# 09-STM32-02.net
KiCad netlist of a schematic drawn in Altium Designer
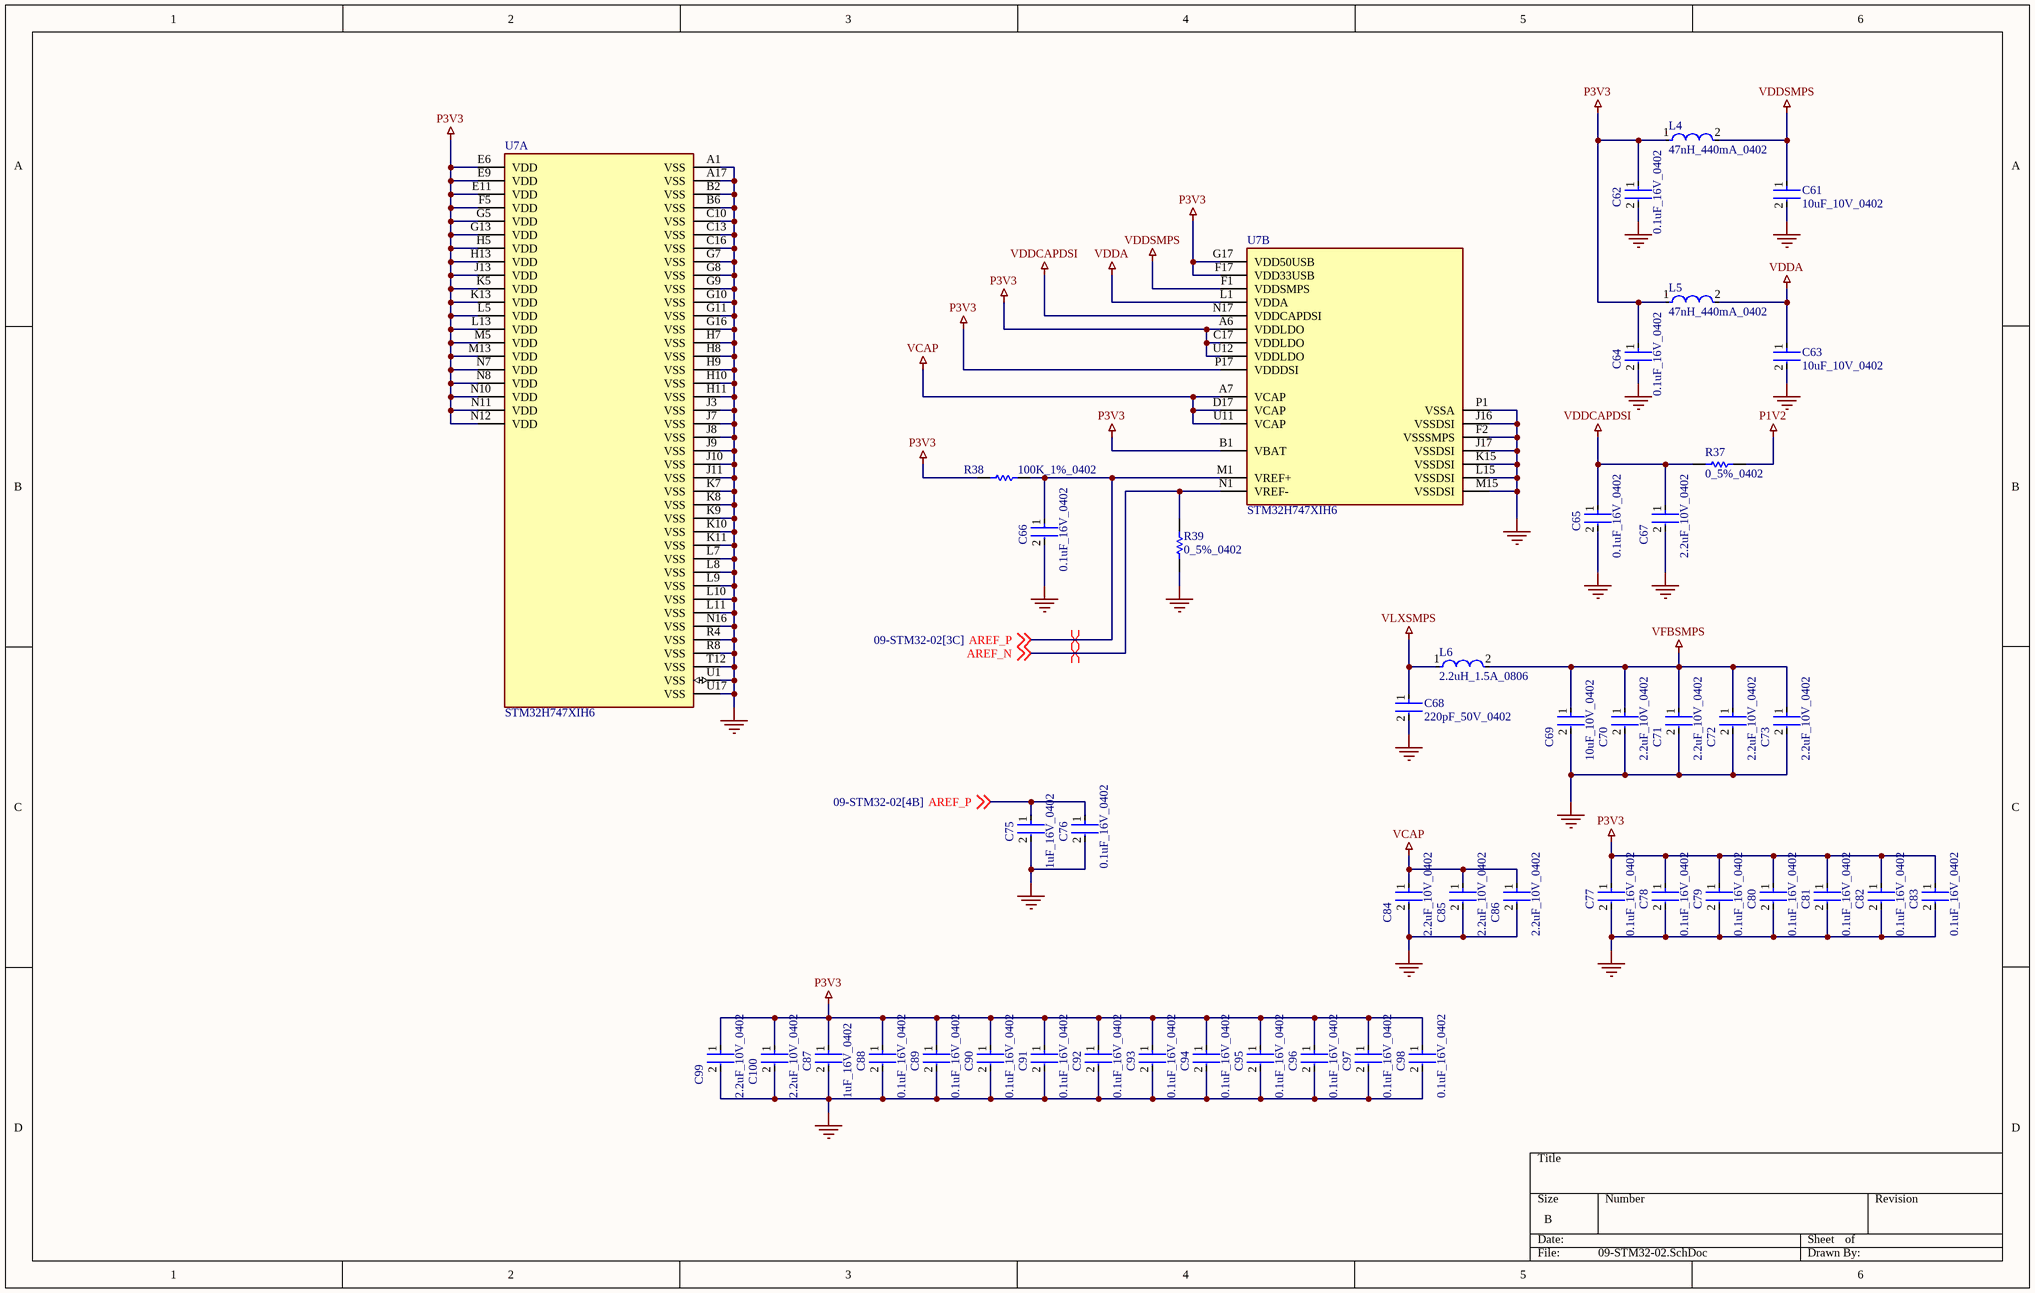
[diagram p0: 09-STM32-02.SchDoc]

(export (version "E")
  (design (tool "Eeschema 10.0.6"))
  (components
    (comp (ref "C61")
      (value "10uF_10V_0402")
      (footprint "FP-CL05A106MP5NUNC-MFG")
      (description "CAP CER 10UF 10V X5R 0402")
      (fields
        (field (name "OCTOPART") "https://octopart.com/cl05a106mp5nunc-samsung-22457395")
        (field (name "TOLERANCE") "20%")
      )
      (libsource (lib "Altium Content Vault") (part "b4654b650e69147ec39a6b967a45e02"))
    )
    (comp (ref "C62")
      (value "0.1uF_16V_0402")
      (footprint "FP-C0402-BB-MFG")
      (description "CAP CER 0.1UF 16V 5% X7R 0402")
      (fields
        (field (name "MANUFACTURER") "Kemet")
        (field (name "MANUFACTURER PART NUMBER") "C0402C104J4RACTU")
      )
      (libsource (lib "Altium Content Vault") (part "b4654b650e69147ec39a6b967a45e02"))
    )
    (comp (ref "C63")
      (value "10uF_10V_0402")
      (footprint "FP-CL05A106MP5NUNC-MFG")
      (description "CAP CER 10UF 10V X5R 0402")
      (fields
        (field (name "OCTOPART") "https://octopart.com/cl05a106mp5nunc-samsung-22457395")
        (field (name "TOLERANCE") "20%")
      )
      (libsource (lib "Altium Content Vault") (part "b4654b650e69147ec39a6b967a45e02"))
    )
    (comp (ref "C64")
      (value "0.1uF_16V_0402")
      (footprint "FP-C0402-BB-MFG")
      (description "CAP CER 0.1UF 16V 5% X7R 0402")
      (fields
        (field (name "MANUFACTURER") "Kemet")
        (field (name "MANUFACTURER PART NUMBER") "C0402C104J4RACTU")
      )
      (libsource (lib "Altium Content Vault") (part "b4654b650e69147ec39a6b967a45e02"))
    )
    (comp (ref "C65")
      (value "0.1uF_16V_0402")
      (footprint "FP-C0402-BB-MFG")
      (description "CAP CER 0.1UF 16V 5% X7R 0402")
      (fields
        (field (name "MANUFACTURER") "Kemet")
        (field (name "MANUFACTURER PART NUMBER") "C0402C104J4RACTU")
      )
      (libsource (lib "Altium Content Vault") (part "b4654b650e69147ec39a6b967a45e02"))
    )
    (comp (ref "C66")
      (value "0.1uF_16V_0402")
      (footprint "FP-C0402-BB-MFG")
      (description "CAP CER 0.1UF 16V 5% X7R 0402")
      (fields
        (field (name "MANUFACTURER") "Kemet")
        (field (name "MANUFACTURER PART NUMBER") "C0402C104J4RACTU")
      )
      (libsource (lib "Altium Content Vault") (part "b4654b650e69147ec39a6b967a45e02"))
    )
    (comp (ref "C67")
      (value "2.2uF_10V_0402")
      (footprint "FP-C1005-050-0_15-0_1-MFG")
      (description "CAP CER 2.2UF 10V X7S 0402")
      (fields (field (name "TOLERANCE") "10%"))
      (libsource (lib "Altium Content Vault") (part "b4654b650e69147ec39a6b967a45e02"))
    )
    (comp (ref "C68")
      (value "220pF_50V_0402")
      (footprint "FP-GCM155-0_05-IPC_C")
      (description "Ceramic Capacitor for Automotive 220pF ±10% 50VDC X7R 0402 Paper T/R")
      (fields (field (name "TOLERANCE") "10%") (field (name "VOLTAGE") "50V"))
      (libsource (lib "Altium Content Vault") (part "02cd4be3c70576c341d710602a673aa"))
    )
    (comp (ref "C69")
      (value "10uF_10V_0402")
      (footprint "FP-CL05A106MP5NUNC-MFG")
      (description "CAP CER 10UF 10V X5R 0402")
      (fields
        (field (name "OCTOPART") "https://octopart.com/cl05a106mp5nunc-samsung-22457395")
        (field (name "TOLERANCE") "20%")
      )
      (libsource (lib "Altium Content Vault") (part "b4654b650e69147ec39a6b967a45e02"))
    )
    (comp (ref "C70")
      (value "2.2uF_10V_0402")
      (footprint "FP-C1005-050-0_15-0_1-MFG")
      (description "CAP CER 2.2UF 10V X7S 0402")
      (fields (field (name "TOLERANCE") "10%"))
      (libsource (lib "Altium Content Vault") (part "b4654b650e69147ec39a6b967a45e02"))
    )
    (comp (ref "C71")
      (value "2.2uF_10V_0402")
      (footprint "FP-C1005-050-0_15-0_1-MFG")
      (description "CAP CER 2.2UF 10V X7S 0402")
      (fields (field (name "TOLERANCE") "10%"))
      (libsource (lib "Altium Content Vault") (part "b4654b650e69147ec39a6b967a45e02"))
    )
    (comp (ref "C72")
      (value "2.2uF_10V_0402")
      (footprint "FP-C1005-050-0_15-0_1-MFG")
      (description "CAP CER 2.2UF 10V X7S 0402")
      (fields (field (name "TOLERANCE") "10%"))
      (libsource (lib "Altium Content Vault") (part "b4654b650e69147ec39a6b967a45e02"))
    )
    (comp (ref "C73")
      (value "2.2uF_10V_0402")
      (footprint "FP-C1005-050-0_15-0_1-MFG")
      (description "CAP CER 2.2UF 10V X7S 0402")
      (fields (field (name "TOLERANCE") "10%"))
      (libsource (lib "Altium Content Vault") (part "b4654b650e69147ec39a6b967a45e02"))
    )
    (comp (ref "C75")
      (value "1uF_16V_0402")
      (footprint "FP-0402-L_1_0_0_05-W_0_5-IPC_A")
      (description "None")
      (fields (field (name "TOLERANCE") "10%"))
      (libsource (lib "Altium Content Vault") (part "b4654b650e69147ec39a6b967a45e02"))
    )
    (comp (ref "C76")
      (value "0.1uF_16V_0402")
      (footprint "FP-C0402-BB-MFG")
      (description "CAP CER 0.1UF 16V 5% X7R 0402")
      (fields
        (field (name "MANUFACTURER") "Kemet")
        (field (name "MANUFACTURER PART NUMBER") "C0402C104J4RACTU")
      )
      (libsource (lib "Altium Content Vault") (part "b4654b650e69147ec39a6b967a45e02"))
    )
    (comp (ref "C77")
      (value "0.1uF_16V_0402")
      (footprint "FP-C0402-BB-MFG")
      (description "CAP CER 0.1UF 16V 5% X7R 0402")
      (fields
        (field (name "MANUFACTURER") "Kemet")
        (field (name "MANUFACTURER PART NUMBER") "C0402C104J4RACTU")
      )
      (libsource (lib "Altium Content Vault") (part "b4654b650e69147ec39a6b967a45e02"))
    )
    (comp (ref "C78")
      (value "0.1uF_16V_0402")
      (footprint "FP-C0402-BB-MFG")
      (description "CAP CER 0.1UF 16V 5% X7R 0402")
      (fields
        (field (name "MANUFACTURER") "Kemet")
        (field (name "MANUFACTURER PART NUMBER") "C0402C104J4RACTU")
      )
      (libsource (lib "Altium Content Vault") (part "b4654b650e69147ec39a6b967a45e02"))
    )
    (comp (ref "C79")
      (value "0.1uF_16V_0402")
      (footprint "FP-C0402-BB-MFG")
      (description "CAP CER 0.1UF 16V 5% X7R 0402")
      (fields
        (field (name "MANUFACTURER") "Kemet")
        (field (name "MANUFACTURER PART NUMBER") "C0402C104J4RACTU")
      )
      (libsource (lib "Altium Content Vault") (part "b4654b650e69147ec39a6b967a45e02"))
    )
    (comp (ref "C80")
      (value "0.1uF_16V_0402")
      (footprint "FP-C0402-BB-MFG")
      (description "CAP CER 0.1UF 16V 5% X7R 0402")
      (fields
        (field (name "MANUFACTURER") "Kemet")
        (field (name "MANUFACTURER PART NUMBER") "C0402C104J4RACTU")
      )
      (libsource (lib "Altium Content Vault") (part "b4654b650e69147ec39a6b967a45e02"))
    )
    (comp (ref "C81")
      (value "0.1uF_16V_0402")
      (footprint "FP-C0402-BB-MFG")
      (description "CAP CER 0.1UF 16V 5% X7R 0402")
      (fields
        (field (name "MANUFACTURER") "Kemet")
        (field (name "MANUFACTURER PART NUMBER") "C0402C104J4RACTU")
      )
      (libsource (lib "Altium Content Vault") (part "b4654b650e69147ec39a6b967a45e02"))
    )
    (comp (ref "C82")
      (value "0.1uF_16V_0402")
      (footprint "FP-C0402-BB-MFG")
      (description "CAP CER 0.1UF 16V 5% X7R 0402")
      (fields
        (field (name "MANUFACTURER") "Kemet")
        (field (name "MANUFACTURER PART NUMBER") "C0402C104J4RACTU")
      )
      (libsource (lib "Altium Content Vault") (part "b4654b650e69147ec39a6b967a45e02"))
    )
    (comp (ref "C83")
      (value "0.1uF_16V_0402")
      (footprint "FP-C0402-BB-MFG")
      (description "CAP CER 0.1UF 16V 5% X7R 0402")
      (fields
        (field (name "MANUFACTURER") "Kemet")
        (field (name "MANUFACTURER PART NUMBER") "C0402C104J4RACTU")
      )
      (libsource (lib "Altium Content Vault") (part "b4654b650e69147ec39a6b967a45e02"))
    )
    (comp (ref "C84")
      (value "2.2uF_10V_0402")
      (footprint "FP-C1005-050-0_15-0_1-MFG")
      (description "CAP CER 2.2UF 10V X7S 0402")
      (fields (field (name "TOLERANCE") "10%"))
      (libsource (lib "Altium Content Vault") (part "b4654b650e69147ec39a6b967a45e02"))
    )
    (comp (ref "C85")
      (value "2.2uF_10V_0402")
      (footprint "FP-C1005-050-0_15-0_1-MFG")
      (description "CAP CER 2.2UF 10V X7S 0402")
      (fields (field (name "TOLERANCE") "10%"))
      (libsource (lib "Altium Content Vault") (part "b4654b650e69147ec39a6b967a45e02"))
    )
    (comp (ref "C86")
      (value "2.2uF_10V_0402")
      (footprint "FP-C1005-050-0_15-0_1-MFG")
      (description "CAP CER 2.2UF 10V X7S 0402")
      (fields (field (name "TOLERANCE") "10%"))
      (libsource (lib "Altium Content Vault") (part "b4654b650e69147ec39a6b967a45e02"))
    )
    (comp (ref "C87")
      (value "1uF_16V_0402")
      (footprint "FP-0402-L_1_0_0_05-W_0_5-IPC_A")
      (description "None")
      (fields (field (name "TOLERANCE") "10%"))
      (libsource (lib "Altium Content Vault") (part "b4654b650e69147ec39a6b967a45e02"))
    )
    (comp (ref "C88")
      (value "0.1uF_16V_0402")
      (footprint "FP-C0402-BB-MFG")
      (description "CAP CER 0.1UF 16V 5% X7R 0402")
      (fields
        (field (name "MANUFACTURER") "Kemet")
        (field (name "MANUFACTURER PART NUMBER") "C0402C104J4RACTU")
      )
      (libsource (lib "Altium Content Vault") (part "b4654b650e69147ec39a6b967a45e02"))
    )
    (comp (ref "C89")
      (value "0.1uF_16V_0402")
      (footprint "FP-C0402-BB-MFG")
      (description "CAP CER 0.1UF 16V 5% X7R 0402")
      (fields
        (field (name "MANUFACTURER") "Kemet")
        (field (name "MANUFACTURER PART NUMBER") "C0402C104J4RACTU")
      )
      (libsource (lib "Altium Content Vault") (part "b4654b650e69147ec39a6b967a45e02"))
    )
    (comp (ref "C90")
      (value "0.1uF_16V_0402")
      (footprint "FP-C0402-BB-MFG")
      (description "CAP CER 0.1UF 16V 5% X7R 0402")
      (fields
        (field (name "MANUFACTURER") "Kemet")
        (field (name "MANUFACTURER PART NUMBER") "C0402C104J4RACTU")
      )
      (libsource (lib "Altium Content Vault") (part "b4654b650e69147ec39a6b967a45e02"))
    )
    (comp (ref "C91")
      (value "0.1uF_16V_0402")
      (footprint "FP-C0402-BB-MFG")
      (description "CAP CER 0.1UF 16V 5% X7R 0402")
      (fields
        (field (name "MANUFACTURER") "Kemet")
        (field (name "MANUFACTURER PART NUMBER") "C0402C104J4RACTU")
      )
      (libsource (lib "Altium Content Vault") (part "b4654b650e69147ec39a6b967a45e02"))
    )
    (comp (ref "C92")
      (value "0.1uF_16V_0402")
      (footprint "FP-C0402-BB-MFG")
      (description "CAP CER 0.1UF 16V 5% X7R 0402")
      (fields
        (field (name "MANUFACTURER") "Kemet")
        (field (name "MANUFACTURER PART NUMBER") "C0402C104J4RACTU")
      )
      (libsource (lib "Altium Content Vault") (part "b4654b650e69147ec39a6b967a45e02"))
    )
    (comp (ref "C93")
      (value "0.1uF_16V_0402")
      (footprint "FP-C0402-BB-MFG")
      (description "CAP CER 0.1UF 16V 5% X7R 0402")
      (fields
        (field (name "MANUFACTURER") "Kemet")
        (field (name "MANUFACTURER PART NUMBER") "C0402C104J4RACTU")
      )
      (libsource (lib "Altium Content Vault") (part "b4654b650e69147ec39a6b967a45e02"))
    )
    (comp (ref "C94")
      (value "0.1uF_16V_0402")
      (footprint "FP-C0402-BB-MFG")
      (description "CAP CER 0.1UF 16V 5% X7R 0402")
      (fields
        (field (name "MANUFACTURER") "Kemet")
        (field (name "MANUFACTURER PART NUMBER") "C0402C104J4RACTU")
      )
      (libsource (lib "Altium Content Vault") (part "b4654b650e69147ec39a6b967a45e02"))
    )
    (comp (ref "C95")
      (value "0.1uF_16V_0402")
      (footprint "FP-C0402-BB-MFG")
      (description "CAP CER 0.1UF 16V 5% X7R 0402")
      (fields
        (field (name "MANUFACTURER") "Kemet")
        (field (name "MANUFACTURER PART NUMBER") "C0402C104J4RACTU")
      )
      (libsource (lib "Altium Content Vault") (part "b4654b650e69147ec39a6b967a45e02"))
    )
    (comp (ref "C96")
      (value "0.1uF_16V_0402")
      (footprint "FP-C0402-BB-MFG")
      (description "CAP CER 0.1UF 16V 5% X7R 0402")
      (fields
        (field (name "MANUFACTURER") "Kemet")
        (field (name "MANUFACTURER PART NUMBER") "C0402C104J4RACTU")
      )
      (libsource (lib "Altium Content Vault") (part "b4654b650e69147ec39a6b967a45e02"))
    )
    (comp (ref "C97")
      (value "0.1uF_16V_0402")
      (footprint "FP-C0402-BB-MFG")
      (description "CAP CER 0.1UF 16V 5% X7R 0402")
      (fields
        (field (name "MANUFACTURER") "Kemet")
        (field (name "MANUFACTURER PART NUMBER") "C0402C104J4RACTU")
      )
      (libsource (lib "Altium Content Vault") (part "b4654b650e69147ec39a6b967a45e02"))
    )
    (comp (ref "C98")
      (value "0.1uF_16V_0402")
      (footprint "FP-C0402-BB-MFG")
      (description "CAP CER 0.1UF 16V 5% X7R 0402")
      (fields
        (field (name "MANUFACTURER") "Kemet")
        (field (name "MANUFACTURER PART NUMBER") "C0402C104J4RACTU")
      )
      (libsource (lib "Altium Content Vault") (part "b4654b650e69147ec39a6b967a45e02"))
    )
    (comp (ref "C99")
      (value "2.2uF_10V_0402")
      (footprint "FP-C1005-050-0_15-0_1-MFG")
      (description "CAP CER 2.2UF 10V X7S 0402")
      (fields (field (name "TOLERANCE") "10%"))
      (libsource (lib "Altium Content Vault") (part "b4654b650e69147ec39a6b967a45e02"))
    )
    (comp (ref "C100")
      (value "2.2uF_10V_0402")
      (footprint "FP-C1005-050-0_15-0_1-MFG")
      (description "CAP CER 2.2UF 10V X7S 0402")
      (fields (field (name "TOLERANCE") "10%"))
      (libsource (lib "Altium Content Vault") (part "b4654b650e69147ec39a6b967a45e02"))
    )
    (comp (ref "L4")
      (value "47nH_440mA_0402")
      (footprint "FP-LQW15AN_80-MFG")
      (description "Wire Wound RF Inductor 47nH ±5% 440mA 0.648Ω 0402 (1005)")
      (fields (field (name "TOLERANCE") "5%"))
      (libsource (lib "Altium Content Vault") (part "725321dda6339637d4d059423bc1c3c"))
    )
    (comp (ref "L5")
      (value "47nH_440mA_0402")
      (footprint "FP-LQW15AN_80-MFG")
      (description "Wire Wound RF Inductor 47nH ±5% 440mA 0.648Ω 0402 (1005)")
      (fields (field (name "TOLERANCE") "5%"))
      (libsource (lib "Altium Content Vault") (part "725321dda6339637d4d059423bc1c3c"))
    )
    (comp (ref "L6")
      (value "2.2uH_1.5A_0806")
      (footprint "FP-DFE201612C-MFG")
      (description "Shielded Wirewound Inductor 2.2uH 20% 1500mA 0.144Ω 0806 (2016)")
      (fields (field (name "TOLERANCE") "20%"))
      (libsource (lib "Altium Content Vault") (part "725321dda6339637d4d059423bc1c3c"))
    )
    (comp (ref "R37")
      (value "0_5%_0402")
      (footprint "RESC1005X40X25NL05T10")
      (fields (field (name "MANUFACTURER") "Panasonic") (field (name "PART NUMBER") "ERJ-U020R00X"))
      (libsource (lib "Altium Content Vault") (part "RES"))
    )
    (comp (ref "R38")
      (value "100K_1%_0402")
      (footprint "RESC1005X40X25ML05T10")
      (fields (field (name "MANUFACTURER") "Yageo") (field (name "PART NUMBER") "RC0402FR-13100KL"))
      (libsource (lib "Altium Content Vault") (part "RES"))
    )
    (comp (ref "R39")
      (value "0_5%_0402")
      (footprint "RESC1005X40X25NL05T10")
      (fields (field (name "MANUFACTURER") "Panasonic") (field (name "PART NUMBER") "ERJ-U020R00X"))
      (libsource (lib "Altium Content Vault") (part "RES"))
    )
    (comp (ref "U7")
      (value "STM32H747XIH6")
      (footprint "FP-TFBGA240+25-A07U-MFG")
      (description "HIGH-PERFORMANCE AND DSP WITH DP")
      (fields
        (field (name "MANUFACTURER") "STMicroelectronics")
        (field (name "OCTOPART") "https://octopart.com/stm32h747xih6-stmicroelectronics-100293943")
      )
      (libsource (lib "Altium Content Vault") (part "41f839bdfd00d9510c8672f0f410bfb"))
    )
  )
  (nets
    (net (code "1") (name "AREF_N") (class "Default")
      (node (ref "R39") (pin "2") (pinfunction "2_2") (pintype "passive"))
      (node (ref "U7") (pin "N1") (pinfunction "VREF-_N1") (pintype "power_in"))
    )
    (net (code "2") (name "AREF_P") (class "Default")
      (node (ref "C66") (pin "1") (pinfunction "1_1") (pintype "passive"))
      (node (ref "C75") (pin "1") (pinfunction "1_1") (pintype "passive"))
      (node (ref "C76") (pin "1") (pinfunction "1_1") (pintype "passive"))
      (node (ref "R38") (pin "2") (pinfunction "2_2") (pintype "passive"))
      (node (ref "U7") (pin "M1") (pinfunction "VREF+_M1") (pintype "power_in"))
    )
    (net (code "3") (name "GND") (class "Default")
      (node (ref "C100") (pin "2") (pinfunction "2_2") (pintype "passive"))
      (node (ref "C61") (pin "2") (pinfunction "2_2") (pintype "passive"))
      (node (ref "C62") (pin "2") (pinfunction "2_2") (pintype "passive"))
      (node (ref "C63") (pin "2") (pinfunction "2_2") (pintype "passive"))
      (node (ref "C64") (pin "2") (pinfunction "2_2") (pintype "passive"))
      (node (ref "C65") (pin "2") (pinfunction "2_2") (pintype "passive"))
      (node (ref "C66") (pin "2") (pinfunction "2_2") (pintype "passive"))
      (node (ref "C67") (pin "2") (pinfunction "2_2") (pintype "passive"))
      (node (ref "C68") (pin "2") (pinfunction "2_2") (pintype "passive"))
      (node (ref "C69") (pin "2") (pinfunction "2_2") (pintype "passive"))
      (node (ref "C70") (pin "2") (pinfunction "2_2") (pintype "passive"))
      (node (ref "C71") (pin "2") (pinfunction "2_2") (pintype "passive"))
      (node (ref "C72") (pin "2") (pinfunction "2_2") (pintype "passive"))
      (node (ref "C73") (pin "2") (pinfunction "2_2") (pintype "passive"))
      (node (ref "C75") (pin "2") (pinfunction "2_2") (pintype "passive"))
      (node (ref "C76") (pin "2") (pinfunction "2_2") (pintype "passive"))
      (node (ref "C77") (pin "2") (pinfunction "2_2") (pintype "passive"))
      (node (ref "C78") (pin "2") (pinfunction "2_2") (pintype "passive"))
      (node (ref "C79") (pin "2") (pinfunction "2_2") (pintype "passive"))
      (node (ref "C80") (pin "2") (pinfunction "2_2") (pintype "passive"))
      (node (ref "C81") (pin "2") (pinfunction "2_2") (pintype "passive"))
      (node (ref "C82") (pin "2") (pinfunction "2_2") (pintype "passive"))
      (node (ref "C83") (pin "2") (pinfunction "2_2") (pintype "passive"))
      (node (ref "C84") (pin "2") (pinfunction "2_2") (pintype "passive"))
      (node (ref "C85") (pin "2") (pinfunction "2_2") (pintype "passive"))
      (node (ref "C86") (pin "2") (pinfunction "2_2") (pintype "passive"))
      (node (ref "C87") (pin "2") (pinfunction "2_2") (pintype "passive"))
      (node (ref "C88") (pin "2") (pinfunction "2_2") (pintype "passive"))
      (node (ref "C89") (pin "2") (pinfunction "2_2") (pintype "passive"))
      (node (ref "C90") (pin "2") (pinfunction "2_2") (pintype "passive"))
      (node (ref "C91") (pin "2") (pinfunction "2_2") (pintype "passive"))
      (node (ref "C92") (pin "2") (pinfunction "2_2") (pintype "passive"))
      (node (ref "C93") (pin "2") (pinfunction "2_2") (pintype "passive"))
      (node (ref "C94") (pin "2") (pinfunction "2_2") (pintype "passive"))
      (node (ref "C95") (pin "2") (pinfunction "2_2") (pintype "passive"))
      (node (ref "C96") (pin "2") (pinfunction "2_2") (pintype "passive"))
      (node (ref "C97") (pin "2") (pinfunction "2_2") (pintype "passive"))
      (node (ref "C98") (pin "2") (pinfunction "2_2") (pintype "passive"))
      (node (ref "C99") (pin "2") (pinfunction "2_2") (pintype "passive"))
      (node (ref "R39") (pin "1") (pinfunction "1_1") (pintype "passive"))
      (node (ref "U7") (pin "A1") (pinfunction "VSS_A1") (pintype "power_in"))
      (node (ref "U7") (pin "A17") (pinfunction "VSS_A17") (pintype "power_in"))
      (node (ref "U7") (pin "B2") (pinfunction "VSS_B2") (pintype "power_in"))
      (node (ref "U7") (pin "B6") (pinfunction "VSS_B6") (pintype "power_in"))
      (node (ref "U7") (pin "C10") (pinfunction "VSS_C10") (pintype "power_in"))
      (node (ref "U7") (pin "C13") (pinfunction "VSS_C13") (pintype "power_in"))
      (node (ref "U7") (pin "C16") (pinfunction "VSS_C16") (pintype "power_in"))
      (node (ref "U7") (pin "F2") (pinfunction "VSSSMPS_F2") (pintype "power_in"))
      (node (ref "U7") (pin "G10") (pinfunction "VSS_G10") (pintype "power_in"))
      (node (ref "U7") (pin "G11") (pinfunction "VSS_G11") (pintype "power_in"))
      (node (ref "U7") (pin "G16") (pinfunction "VSS_G16") (pintype "power_in"))
      (node (ref "U7") (pin "G7") (pinfunction "VSS_G7") (pintype "power_in"))
      (node (ref "U7") (pin "G8") (pinfunction "VSS_G8") (pintype "power_in"))
      (node (ref "U7") (pin "G9") (pinfunction "VSS_G9") (pintype "power_in"))
      (node (ref "U7") (pin "H10") (pinfunction "VSS_H10") (pintype "power_in"))
      (node (ref "U7") (pin "H11") (pinfunction "VSS_H11") (pintype "power_in"))
      (node (ref "U7") (pin "H7") (pinfunction "VSS_H7") (pintype "power_in"))
      (node (ref "U7") (pin "H8") (pinfunction "VSS_H8") (pintype "power_in"))
      (node (ref "U7") (pin "H9") (pinfunction "VSS_H9") (pintype "power_in"))
      (node (ref "U7") (pin "J10") (pinfunction "VSS_J10") (pintype "power_in"))
      (node (ref "U7") (pin "J11") (pinfunction "VSS_J11") (pintype "power_in"))
      (node (ref "U7") (pin "J16") (pinfunction "VSSDSI_J16") (pintype "power_in"))
      (node (ref "U7") (pin "J17") (pinfunction "VSSDSI_J17") (pintype "power_in"))
      (node (ref "U7") (pin "J3") (pinfunction "VSS_J3") (pintype "power_in"))
      (node (ref "U7") (pin "J7") (pinfunction "VSS_J7") (pintype "power_in"))
      (node (ref "U7") (pin "J8") (pinfunction "VSS_J8") (pintype "power_in"))
      (node (ref "U7") (pin "J9") (pinfunction "VSS_J9") (pintype "power_in"))
      (node (ref "U7") (pin "K10") (pinfunction "VSS_K10") (pintype "power_in"))
      (node (ref "U7") (pin "K11") (pinfunction "VSS_K11") (pintype "power_in"))
      (node (ref "U7") (pin "K15") (pinfunction "VSSDSI_K15") (pintype "power_in"))
      (node (ref "U7") (pin "K7") (pinfunction "VSS_K7") (pintype "power_in"))
      (node (ref "U7") (pin "K8") (pinfunction "VSS_K8") (pintype "power_in"))
      (node (ref "U7") (pin "K9") (pinfunction "VSS_K9") (pintype "power_in"))
      (node (ref "U7") (pin "L10") (pinfunction "VSS_L10") (pintype "power_in"))
      (node (ref "U7") (pin "L11") (pinfunction "VSS_L11") (pintype "power_in"))
      (node (ref "U7") (pin "L15") (pinfunction "VSSDSI_L15") (pintype "power_in"))
      (node (ref "U7") (pin "L7") (pinfunction "VSS_L7") (pintype "power_in"))
      (node (ref "U7") (pin "L8") (pinfunction "VSS_L8") (pintype "power_in"))
      (node (ref "U7") (pin "L9") (pinfunction "VSS_L9") (pintype "power_in"))
      (node (ref "U7") (pin "M15") (pinfunction "VSSDSI_M15") (pintype "power_in"))
      (node (ref "U7") (pin "N16") (pinfunction "VSS_N16") (pintype "power_in"))
      (node (ref "U7") (pin "P1") (pinfunction "VSSA_P1") (pintype "power_in"))
      (node (ref "U7") (pin "R4") (pinfunction "VSS_R4") (pintype "power_in"))
      (node (ref "U7") (pin "R8") (pinfunction "VSS_R8") (pintype "power_in"))
      (node (ref "U7") (pin "T12") (pinfunction "VSS_T12") (pintype "power_in"))
      (node (ref "U7") (pin "U1") (pinfunction "VSS_U1") (pintype "bidirectional"))
      (node (ref "U7") (pin "U17") (pinfunction "VSS_U17") (pintype "power_in"))
    )
    (net (code "4") (name "P1V2") (class "Default")
      (node (ref "R37") (pin "1") (pinfunction "1_1") (pintype "passive"))
    )
    (net (code "5") (name "P3V3") (class "Default")
      (node (ref "C100") (pin "1") (pinfunction "1_1") (pintype "passive"))
      (node (ref "C62") (pin "1") (pinfunction "1_1") (pintype "passive"))
      (node (ref "C64") (pin "1") (pinfunction "1_1") (pintype "passive"))
      (node (ref "C77") (pin "1") (pinfunction "1_1") (pintype "passive"))
      (node (ref "C78") (pin "1") (pinfunction "1_1") (pintype "passive"))
      (node (ref "C79") (pin "1") (pinfunction "1_1") (pintype "passive"))
      (node (ref "C80") (pin "1") (pinfunction "1_1") (pintype "passive"))
      (node (ref "C81") (pin "1") (pinfunction "1_1") (pintype "passive"))
      (node (ref "C82") (pin "1") (pinfunction "1_1") (pintype "passive"))
      (node (ref "C83") (pin "1") (pinfunction "1_1") (pintype "passive"))
      (node (ref "C87") (pin "1") (pinfunction "1_1") (pintype "passive"))
      (node (ref "C88") (pin "1") (pinfunction "1_1") (pintype "passive"))
      (node (ref "C89") (pin "1") (pinfunction "1_1") (pintype "passive"))
      (node (ref "C90") (pin "1") (pinfunction "1_1") (pintype "passive"))
      (node (ref "C91") (pin "1") (pinfunction "1_1") (pintype "passive"))
      (node (ref "C92") (pin "1") (pinfunction "1_1") (pintype "passive"))
      (node (ref "C93") (pin "1") (pinfunction "1_1") (pintype "passive"))
      (node (ref "C94") (pin "1") (pinfunction "1_1") (pintype "passive"))
      (node (ref "C95") (pin "1") (pinfunction "1_1") (pintype "passive"))
      (node (ref "C96") (pin "1") (pinfunction "1_1") (pintype "passive"))
      (node (ref "C97") (pin "1") (pinfunction "1_1") (pintype "passive"))
      (node (ref "C98") (pin "1") (pinfunction "1_1") (pintype "passive"))
      (node (ref "C99") (pin "1") (pinfunction "1_1") (pintype "passive"))
      (node (ref "L4") (pin "1") (pinfunction "1_1") (pintype "passive"))
      (node (ref "L5") (pin "1") (pinfunction "1_1") (pintype "passive"))
      (node (ref "R38") (pin "1") (pinfunction "1_1") (pintype "passive"))
      (node (ref "U7") (pin "A6") (pinfunction "VDDLDO_A6") (pintype "power_in"))
      (node (ref "U7") (pin "B1") (pinfunction "VBAT_B1") (pintype "power_in"))
      (node (ref "U7") (pin "C17") (pinfunction "VDDLDO_C17") (pintype "power_in"))
      (node (ref "U7") (pin "E11") (pinfunction "VDD_E11") (pintype "power_in"))
      (node (ref "U7") (pin "E6") (pinfunction "VDD_E6") (pintype "power_in"))
      (node (ref "U7") (pin "E9") (pinfunction "VDD_E9") (pintype "power_in"))
      (node (ref "U7") (pin "F17") (pinfunction "VDD33USB_F17") (pintype "power_in"))
      (node (ref "U7") (pin "F5") (pinfunction "VDD_F5") (pintype "power_in"))
      (node (ref "U7") (pin "G13") (pinfunction "VDD_G13") (pintype "power_in"))
      (node (ref "U7") (pin "G17") (pinfunction "VDD50USB_G17") (pintype "power_in"))
      (node (ref "U7") (pin "G5") (pinfunction "VDD_G5") (pintype "power_in"))
      (node (ref "U7") (pin "H13") (pinfunction "VDD_H13") (pintype "power_in"))
      (node (ref "U7") (pin "H5") (pinfunction "VDD_H5") (pintype "power_in"))
      (node (ref "U7") (pin "J13") (pinfunction "VDD_J13") (pintype "power_in"))
      (node (ref "U7") (pin "K13") (pinfunction "VDD_K13") (pintype "power_in"))
      (node (ref "U7") (pin "K5") (pinfunction "VDD_K5") (pintype "power_in"))
      (node (ref "U7") (pin "L13") (pinfunction "VDD_L13") (pintype "power_in"))
      (node (ref "U7") (pin "L5") (pinfunction "VDD_L5") (pintype "power_in"))
      (node (ref "U7") (pin "M13") (pinfunction "VDD_M13") (pintype "power_in"))
      (node (ref "U7") (pin "M5") (pinfunction "VDD_M5") (pintype "power_in"))
      (node (ref "U7") (pin "N10") (pinfunction "VDD_N10") (pintype "power_in"))
      (node (ref "U7") (pin "N11") (pinfunction "VDD_N11") (pintype "power_in"))
      (node (ref "U7") (pin "N12") (pinfunction "VDD_N12") (pintype "power_in"))
      (node (ref "U7") (pin "N7") (pinfunction "VDD_N7") (pintype "power_in"))
      (node (ref "U7") (pin "N8") (pinfunction "VDD_N8") (pintype "power_in"))
      (node (ref "U7") (pin "P17") (pinfunction "VDDDSI_P17") (pintype "power_in"))
      (node (ref "U7") (pin "U12") (pinfunction "VDDLDO_U12") (pintype "power_in"))
    )
    (net (code "6") (name "VCAP") (class "Default")
      (node (ref "C84") (pin "1") (pinfunction "1_1") (pintype "passive"))
      (node (ref "C85") (pin "1") (pinfunction "1_1") (pintype "passive"))
      (node (ref "C86") (pin "1") (pinfunction "1_1") (pintype "passive"))
      (node (ref "U7") (pin "A7") (pinfunction "VCAP_A7") (pintype "power_in"))
      (node (ref "U7") (pin "D17") (pinfunction "VCAP_D17") (pintype "power_in"))
      (node (ref "U7") (pin "U11") (pinfunction "VCAP_U11") (pintype "power_in"))
    )
    (net (code "7") (name "VDDA") (class "Default")
      (node (ref "C63") (pin "1") (pinfunction "1_1") (pintype "passive"))
      (node (ref "L5") (pin "2") (pinfunction "2_2") (pintype "passive"))
      (node (ref "U7") (pin "L1") (pinfunction "VDDA_L1") (pintype "power_in"))
    )
    (net (code "8") (name "VDDCAPDSI") (class "Default")
      (node (ref "C65") (pin "1") (pinfunction "1_1") (pintype "passive"))
      (node (ref "C67") (pin "1") (pinfunction "1_1") (pintype "passive"))
      (node (ref "R37") (pin "2") (pinfunction "2_2") (pintype "passive"))
      (node (ref "U7") (pin "N17") (pinfunction "VDDCAPDSI_N17") (pintype "power_in"))
    )
    (net (code "9") (name "VDDSMPS") (class "Default")
      (node (ref "C61") (pin "1") (pinfunction "1_1") (pintype "passive"))
      (node (ref "L4") (pin "2") (pinfunction "2_2") (pintype "passive"))
      (node (ref "U7") (pin "F1") (pinfunction "VDDSMPS_F1") (pintype "power_in"))
    )
    (net (code "10") (name "VFBSMPS") (class "Default")
      (node (ref "C69") (pin "1") (pinfunction "1_1") (pintype "passive"))
      (node (ref "C70") (pin "1") (pinfunction "1_1") (pintype "passive"))
      (node (ref "C71") (pin "1") (pinfunction "1_1") (pintype "passive"))
      (node (ref "C72") (pin "1") (pinfunction "1_1") (pintype "passive"))
      (node (ref "C73") (pin "1") (pinfunction "1_1") (pintype "passive"))
      (node (ref "L6") (pin "2") (pinfunction "2_2") (pintype "passive"))
    )
    (net (code "11") (name "VLXSMPS") (class "Default")
      (node (ref "C68") (pin "1") (pinfunction "1_1") (pintype "passive"))
      (node (ref "L6") (pin "1") (pinfunction "1_1") (pintype "passive"))
    )
  )
)
